# Power.net
KiCad netlist of a schematic drawn in Altium Designer
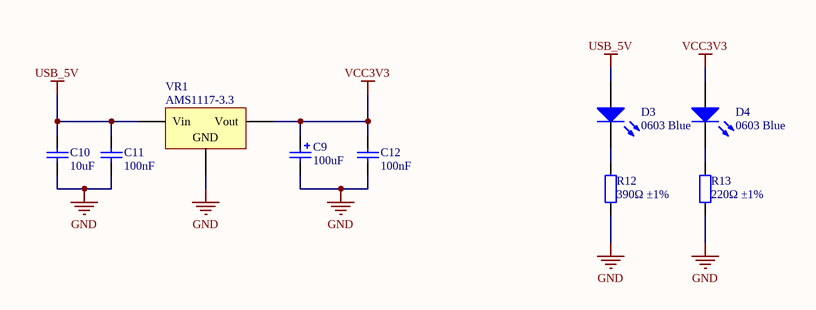
[diagram p0: Power.SchDoc]

(export (version "E")
  (design (tool "Eeschema 10.0.6"))
  (components
    (comp (ref "C9")
      (value "100uF")
      (footprint "CASE-B_3528")
      (description "Tantalum capacitor")
      (fields (field (name "MANUFACTURER") "AVX") (field (name "PARTNUMBER") "TAJB107K006RNJ"))
      (libsource (lib "Cap") (part "3528 100uF (107) 10% 6.3V"))
    )
    (comp (ref "C10")
      (value "10uF")
      (footprint "1206_C")
      (description "Chip capacitors")
      (fields
        (field (name "MANUFACTURER") "Samsung Electro-Mechanics")
        (field (name "PARTNUMBER") "CL31A106KBHNNNE")
      )
      (libsource (lib "Cap") (part "1206 10uF (106) 10% 50V"))
    )
    (comp (ref "C11")
      (value "100nF")
      (footprint "0402_C")
      (description "Chip capacitors")
      (fields
        (field (name "MANUFACTURER") "Samsung Electro-Mechanics")
        (field (name "PARTNUMBER") "CL05B104KO5NNNC")
      )
      (libsource (lib "Miscellaneous Devices LC") (part "0402 100nF (104) 10% 16V"))
    )
    (comp (ref "C12")
      (value "100nF")
      (footprint "1206_C")
      (description "Chip capacitors")
      (fields
        (field (name "MANUFACTURER") "Samsung Electro-Mechanics")
        (field (name "PARTNUMBER") "CL31B104KBCNNNC")
      )
      (libsource (lib "Miscellaneous Devices LC") (part "1206 100nF (104) 10% 50V"))
    )
    (comp (ref "D3")
      (value "0603 Blue")
      (footprint "0603_LED_S1")
      (description "LED")
      (libsource (lib "Miscellaneous Devices LC") (part "0603 LED Blue"))
    )
    (comp (ref "D4")
      (value "0603 Blue")
      (footprint "0603_LED_S1")
      (description "LED")
      (libsource (lib "Miscellaneous Devices LC") (part "0603 LED Blue"))
    )
    (comp (ref "R12")
      (value "390Ω ±1%")
      (footprint "0603_R")
      (description "Chip resistor")
      (fields (field (name "MANUFACTURER") "Uniroyal Elec") (field (name "PARTNUMBER") "0603WAF3900T5E"))
      (libsource (lib "RES") (part "0603 390R (3900) 1%"))
    )
    (comp (ref "R13")
      (value "220Ω ±1%")
      (footprint "0402_R")
      (description "Chip resistor")
      (fields (field (name "MANUFACTURER") "Uniroyal Elec") (field (name "PARTNUMBER") "0402WGF2200TCE"))
      (libsource (lib "RES") (part "0402 220R (2200) 1%"))
    )
    (comp (ref "VR1")
      (value "AMS1117-3.3")
      (footprint "SOT-223")
      (description "低压差线性稳压(LDO)")
      (libsource (lib "Miscellaneous Devices LC") (part "SOT-223 AMS1117-3.3"))
    )
  )
  (nets
    (net (code "1") (name "GND") (class "Default")
      (node (ref "C10") (pin "1") (pinfunction "1_1") (pintype "passive"))
      (node (ref "C11") (pin "1") (pinfunction "1_1") (pintype "passive"))
      (node (ref "C12") (pin "1") (pinfunction "1_1") (pintype "passive"))
      (node (ref "C9") (pin "2") (pinfunction "2_2") (pintype "passive"))
      (node (ref "R12") (pin "1") (pinfunction "1_1") (pintype "passive"))
      (node (ref "R13") (pin "1") (pinfunction "1_1") (pintype "passive"))
      (node (ref "VR1") (pin "1") (pinfunction "GND_1") (pintype "passive"))
    )
    (net (code "2") (name "Net-(D3-PadK)") (class "Default")
      (node (ref "D3") (pin "K") (pinfunction "K_K") (pintype "passive"))
      (node (ref "R12") (pin "2") (pinfunction "2_2") (pintype "passive"))
    )
    (net (code "3") (name "Net-(D4-PadK)") (class "Default")
      (node (ref "D4") (pin "K") (pinfunction "K_K") (pintype "passive"))
      (node (ref "R13") (pin "2") (pinfunction "2_2") (pintype "passive"))
    )
    (net (code "4") (name "USB_5V") (class "Default")
      (node (ref "C10") (pin "2") (pinfunction "2_2") (pintype "passive"))
      (node (ref "C11") (pin "2") (pinfunction "2_2") (pintype "passive"))
      (node (ref "D3") (pin "A") (pinfunction "A_A") (pintype "passive"))
      (node (ref "VR1") (pin "3") (pinfunction "Vin_3") (pintype "passive"))
    )
    (net (code "5") (name "VCC3V3") (class "Default")
      (node (ref "C12") (pin "2") (pinfunction "2_2") (pintype "passive"))
      (node (ref "C9") (pin "1") (pinfunction "1_1") (pintype "passive"))
      (node (ref "D4") (pin "A") (pinfunction "A_A") (pintype "passive"))
      (node (ref "VR1") (pin "2") (pinfunction "Vout_2") (pintype "passive"))
    )
  )
)
